# Pink-Noise-Generator-Thomas-Henry.net
KiCad netlist of a schematic drawn in EAGLE
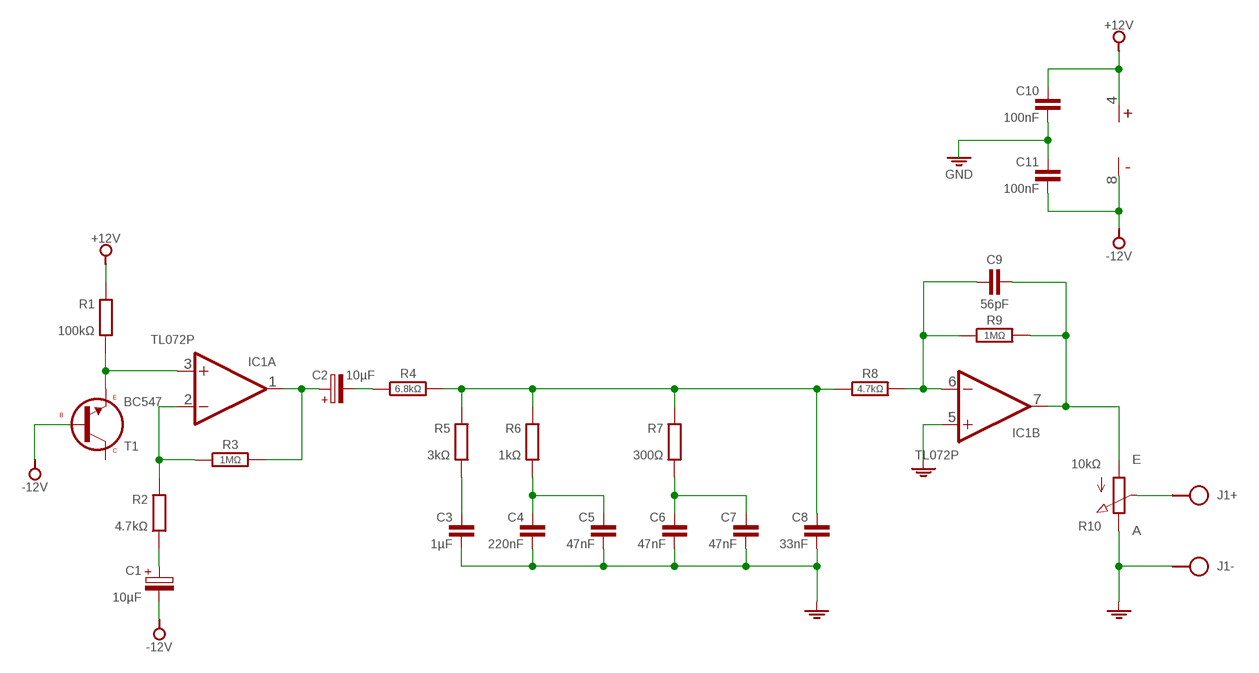
[diagram p0: schematic, sheet 1]

(export (version "E")
  (design (tool "Eeschema 10.0.6"))
  (components
    (comp (ref "C1")
      (value "10µF")
      (footprint "eagle-import:E2,5-5")
      (libsource (lib "eagle-import") (part "CPOLE2.5-5"))
    )
    (comp (ref "C2")
      (value "10µF")
      (footprint "eagle-import:E2,5-5")
      (libsource (lib "eagle-import") (part "CPOL-HE2,5-5"))
    )
    (comp (ref "C3")
      (value "1µF")
      (footprint "eagle-import:C050-020X044_V")
      (libsource (lib "eagle-import") (part "C050-020X044/V"))
    )
    (comp (ref "C4")
      (value "220nF")
      (footprint "eagle-import:C050-020X044_V")
      (libsource (lib "eagle-import") (part "C050-020X044/V"))
    )
    (comp (ref "C5")
      (value "47nF")
      (footprint "eagle-import:C050-020X044_V")
      (libsource (lib "eagle-import") (part "C050-020X044/V"))
    )
    (comp (ref "C6")
      (value "47nF")
      (footprint "eagle-import:C050-020X044_V")
      (libsource (lib "eagle-import") (part "C050-020X044/V"))
    )
    (comp (ref "C7")
      (value "47nF")
      (footprint "eagle-import:C050-020X044_V")
      (libsource (lib "eagle-import") (part "C050-020X044/V"))
    )
    (comp (ref "C8")
      (value "33nF")
      (footprint "eagle-import:C050-020X044_V")
      (libsource (lib "eagle-import") (part "C050-020X044/V"))
    )
    (comp (ref "C9")
      (value "56pF")
      (footprint "eagle-import:C050-020X036")
      (libsource (lib "eagle-import") (part "C-H050-020X036"))
    )
    (comp (ref "C10")
      (value "100nF")
      (footprint "eagle-import:C050-020X044_V")
      (libsource (lib "eagle-import") (part "C050-020X044/V"))
    )
    (comp (ref "C11")
      (value "100nF")
      (footprint "eagle-import:C050-020X044_V")
      (libsource (lib "eagle-import") (part "C050-020X044/V"))
    )
    (comp (ref "IC1")
      (value "TL072P")
      (footprint "eagle-import:DIL08")
      (libsource (lib "eagle-import") (part "TL072P"))
    )
    (comp (ref "J1")
      (value "SPAD+-+-")
      (footprint "eagle-import:SPAD+-")
      (libsource (lib "eagle-import") (part "SPAD+-+-"))
    )
    (comp (ref "PWR1")
      (value "-12V_GND_+12V-VCC-VEE")
      (footprint "eagle-import:SPAD-PWR-+GND-")
      (libsource (lib "eagle-import") (part "-12V_GND_+12V-VCC-VEE"))
    )
    (comp (ref "R1")
      (value "100kΩ")
      (footprint "eagle-import:0204_10-V")
      (libsource (lib "eagle-import") (part "R0204/10-V"))
    )
    (comp (ref "R2")
      (value "4.7kΩ")
      (footprint "eagle-import:0204_10-V")
      (libsource (lib "eagle-import") (part "R0204/10-V"))
    )
    (comp (ref "R3")
      (value "1MΩ")
      (footprint "eagle-import:0204_10")
      (libsource (lib "eagle-import") (part "R-H0204/10"))
    )
    (comp (ref "R4")
      (value "6.8kΩ")
      (footprint "eagle-import:0204_10")
      (libsource (lib "eagle-import") (part "R-H0204/10"))
    )
    (comp (ref "R5")
      (value "3kΩ")
      (footprint "eagle-import:0204_10-V")
      (libsource (lib "eagle-import") (part "R0204/10-V"))
    )
    (comp (ref "R6")
      (value "1kΩ")
      (footprint "eagle-import:0204_10-V")
      (libsource (lib "eagle-import") (part "R0204/10-V"))
    )
    (comp (ref "R7")
      (value "300Ω")
      (footprint "eagle-import:0204_10-V")
      (libsource (lib "eagle-import") (part "R0204/10-V"))
    )
    (comp (ref "R8")
      (value "4.7kΩ")
      (footprint "eagle-import:0204_10")
      (libsource (lib "eagle-import") (part "R-H0204/10"))
    )
    (comp (ref "R9")
      (value "1MΩ")
      (footprint "eagle-import:0204_10")
      (libsource (lib "eagle-import") (part "R-H0204/10"))
    )
    (comp (ref "R10")
      (value "10kΩ")
      (footprint "eagle-import:POT")
      (libsource (lib "eagle-import") (part "POT"))
    )
    (comp (ref "T1")
      (value "BC547")
      (footprint "eagle-import:TO92")
      (libsource (lib "eagle-import") (part "BC547"))
    )
  )
  (nets
    (net (code "1") (name "+12V") (class "Default")
      (node (ref "C10") (pin "1") (pinfunction "1_1") (pintype "passive"))
      (node (ref "IC1") (pin "4") (pinfunction "+15V_4") (pintype "power_in"))
      (node (ref "PWR1") (pin "VCC") (pinfunction "+12V_VCC") (pintype "power_in"))
      (node (ref "R1") (pin "1") (pinfunction "2_1") (pintype "passive"))
    )
    (net (code "2") (name "-12V") (class "Default")
      (node (ref "C1") (pin "-") (pinfunction "-_-") (pintype "passive"))
      (node (ref "C11") (pin "2") (pinfunction "2_2") (pintype "passive"))
      (node (ref "IC1") (pin "8") (pinfunction "-15V_8") (pintype "power_in"))
      (node (ref "PWR1") (pin "VEE") (pinfunction "-12V_VEE") (pintype "power_in"))
      (node (ref "T1") (pin "2") (pinfunction "B_2") (pintype "passive"))
    )
    (net (code "3") (name "GND") (class "Default")
      (node (ref "C10") (pin "2") (pinfunction "2_2") (pintype "passive"))
      (node (ref "C11") (pin "1") (pinfunction "1_1") (pintype "passive"))
      (node (ref "C3") (pin "2") (pinfunction "2_2") (pintype "passive"))
      (node (ref "C4") (pin "2") (pinfunction "2_2") (pintype "passive"))
      (node (ref "C5") (pin "2") (pinfunction "2_2") (pintype "passive"))
      (node (ref "C6") (pin "2") (pinfunction "2_2") (pintype "passive"))
      (node (ref "C7") (pin "2") (pinfunction "2_2") (pintype "passive"))
      (node (ref "C8") (pin "2") (pinfunction "2_2") (pintype "passive"))
      (node (ref "IC1") (pin "5") (pinfunction "+IN_5") (pintype "input"))
      (node (ref "J1") (pin "1") (pinfunction "P$1_1") (pintype "passive"))
      (node (ref "PWR1") (pin "GND") (pinfunction "GND_GND") (pintype "power_in"))
      (node (ref "R10") (pin "E") (pinfunction "E_E") (pintype "passive"))
    )
    (net (code "4") (name "Net-(C2-Pad-)") (class "Default")
      (node (ref "C2") (pin "-") (pinfunction "-_-") (pintype "passive"))
      (node (ref "R4") (pin "1") (pinfunction "1_1") (pintype "passive"))
    )
    (net (code "5") (name "Net-(IC1B-+IN)") (class "Default")
      (node (ref "IC1") (pin "3") (pinfunction "+IN_3") (pintype "input"))
      (node (ref "R1") (pin "2") (pinfunction "1_2") (pintype "passive"))
      (node (ref "T1") (pin "3") (pinfunction "E_3") (pintype "passive"))
    )
    (net (code "6") (name "Net-(IC1B--IN)") (class "Default")
      (node (ref "IC1") (pin "2") (pinfunction "-IN_2") (pintype "input"))
      (node (ref "R2") (pin "1") (pinfunction "2_1") (pintype "passive"))
      (node (ref "R3") (pin "1") (pinfunction "1_1") (pintype "passive"))
    )
    (net (code "7") (name "Net-(IC1B-OUT)") (class "Default")
      (node (ref "C2") (pin "+") (pinfunction "+_+") (pintype "passive"))
      (node (ref "IC1") (pin "1") (pinfunction "OUT_1") (pintype "output"))
      (node (ref "R3") (pin "2") (pinfunction "2_2") (pintype "passive"))
    )
    (net (code "8") (name "Net-(IC1C--IN)") (class "Default")
      (node (ref "C9") (pin "1") (pinfunction "1_1") (pintype "passive"))
      (node (ref "IC1") (pin "6") (pinfunction "-IN_6") (pintype "input"))
      (node (ref "R8") (pin "2") (pinfunction "2_2") (pintype "passive"))
      (node (ref "R9") (pin "1") (pinfunction "1_1") (pintype "passive"))
    )
    (net (code "9") (name "Net-(IC1C-OUT)") (class "Default")
      (node (ref "C9") (pin "2") (pinfunction "2_2") (pintype "passive"))
      (node (ref "IC1") (pin "7") (pinfunction "OUT_7") (pintype "output"))
      (node (ref "R10") (pin "A") (pinfunction "A_A") (pintype "passive"))
      (node (ref "R9") (pin "2") (pinfunction "2_2") (pintype "passive"))
    )
    (net (code "10") (name "Net-(J1A-P$1)") (class "Default")
      (node (ref "J1") (pin "2") (pinfunction "P$1_2") (pintype "passive"))
      (node (ref "R10") (pin "S") (pinfunction "S_S") (pintype "passive"))
    )
    (net (code "11") (name "Net-(R2-1)") (class "Default")
      (node (ref "C1") (pin "+") (pinfunction "+_+") (pintype "passive"))
      (node (ref "R2") (pin "2") (pinfunction "1_2") (pintype "passive"))
    )
    (net (code "12") (name "Net-(R5-1)") (class "Default")
      (node (ref "C3") (pin "1") (pinfunction "1_1") (pintype "passive"))
      (node (ref "R5") (pin "2") (pinfunction "1_2") (pintype "passive"))
    )
    (net (code "13") (name "Net-(R5-2)") (class "Default")
      (node (ref "C8") (pin "1") (pinfunction "1_1") (pintype "passive"))
      (node (ref "R4") (pin "2") (pinfunction "2_2") (pintype "passive"))
      (node (ref "R5") (pin "1") (pinfunction "2_1") (pintype "passive"))
      (node (ref "R6") (pin "1") (pinfunction "2_1") (pintype "passive"))
      (node (ref "R7") (pin "1") (pinfunction "2_1") (pintype "passive"))
      (node (ref "R8") (pin "1") (pinfunction "1_1") (pintype "passive"))
    )
    (net (code "14") (name "Net-(R6-1)") (class "Default")
      (node (ref "C4") (pin "1") (pinfunction "1_1") (pintype "passive"))
      (node (ref "C5") (pin "1") (pinfunction "1_1") (pintype "passive"))
      (node (ref "R6") (pin "2") (pinfunction "1_2") (pintype "passive"))
    )
    (net (code "15") (name "Net-(R7-1)") (class "Default")
      (node (ref "C6") (pin "1") (pinfunction "1_1") (pintype "passive"))
      (node (ref "C7") (pin "1") (pinfunction "1_1") (pintype "passive"))
      (node (ref "R7") (pin "2") (pinfunction "1_2") (pintype "passive"))
    )
    (net (code "16") (name "unconnected-(T1-C-Pad1)") (class "Default")
      (node (ref "T1") (pin "1") (pinfunction "C_1") (pintype "passive"))
    )
  )
)
